# TestBench_rev3.net
KiCad netlist of a schematic drawn in EAGLE
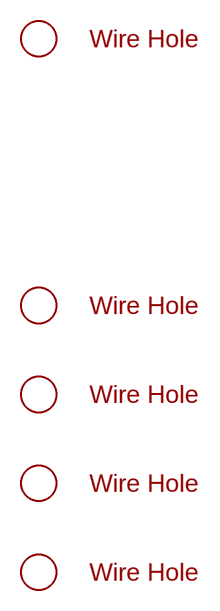
[diagram p0: schematic, sheet 1, part 1 of 2]
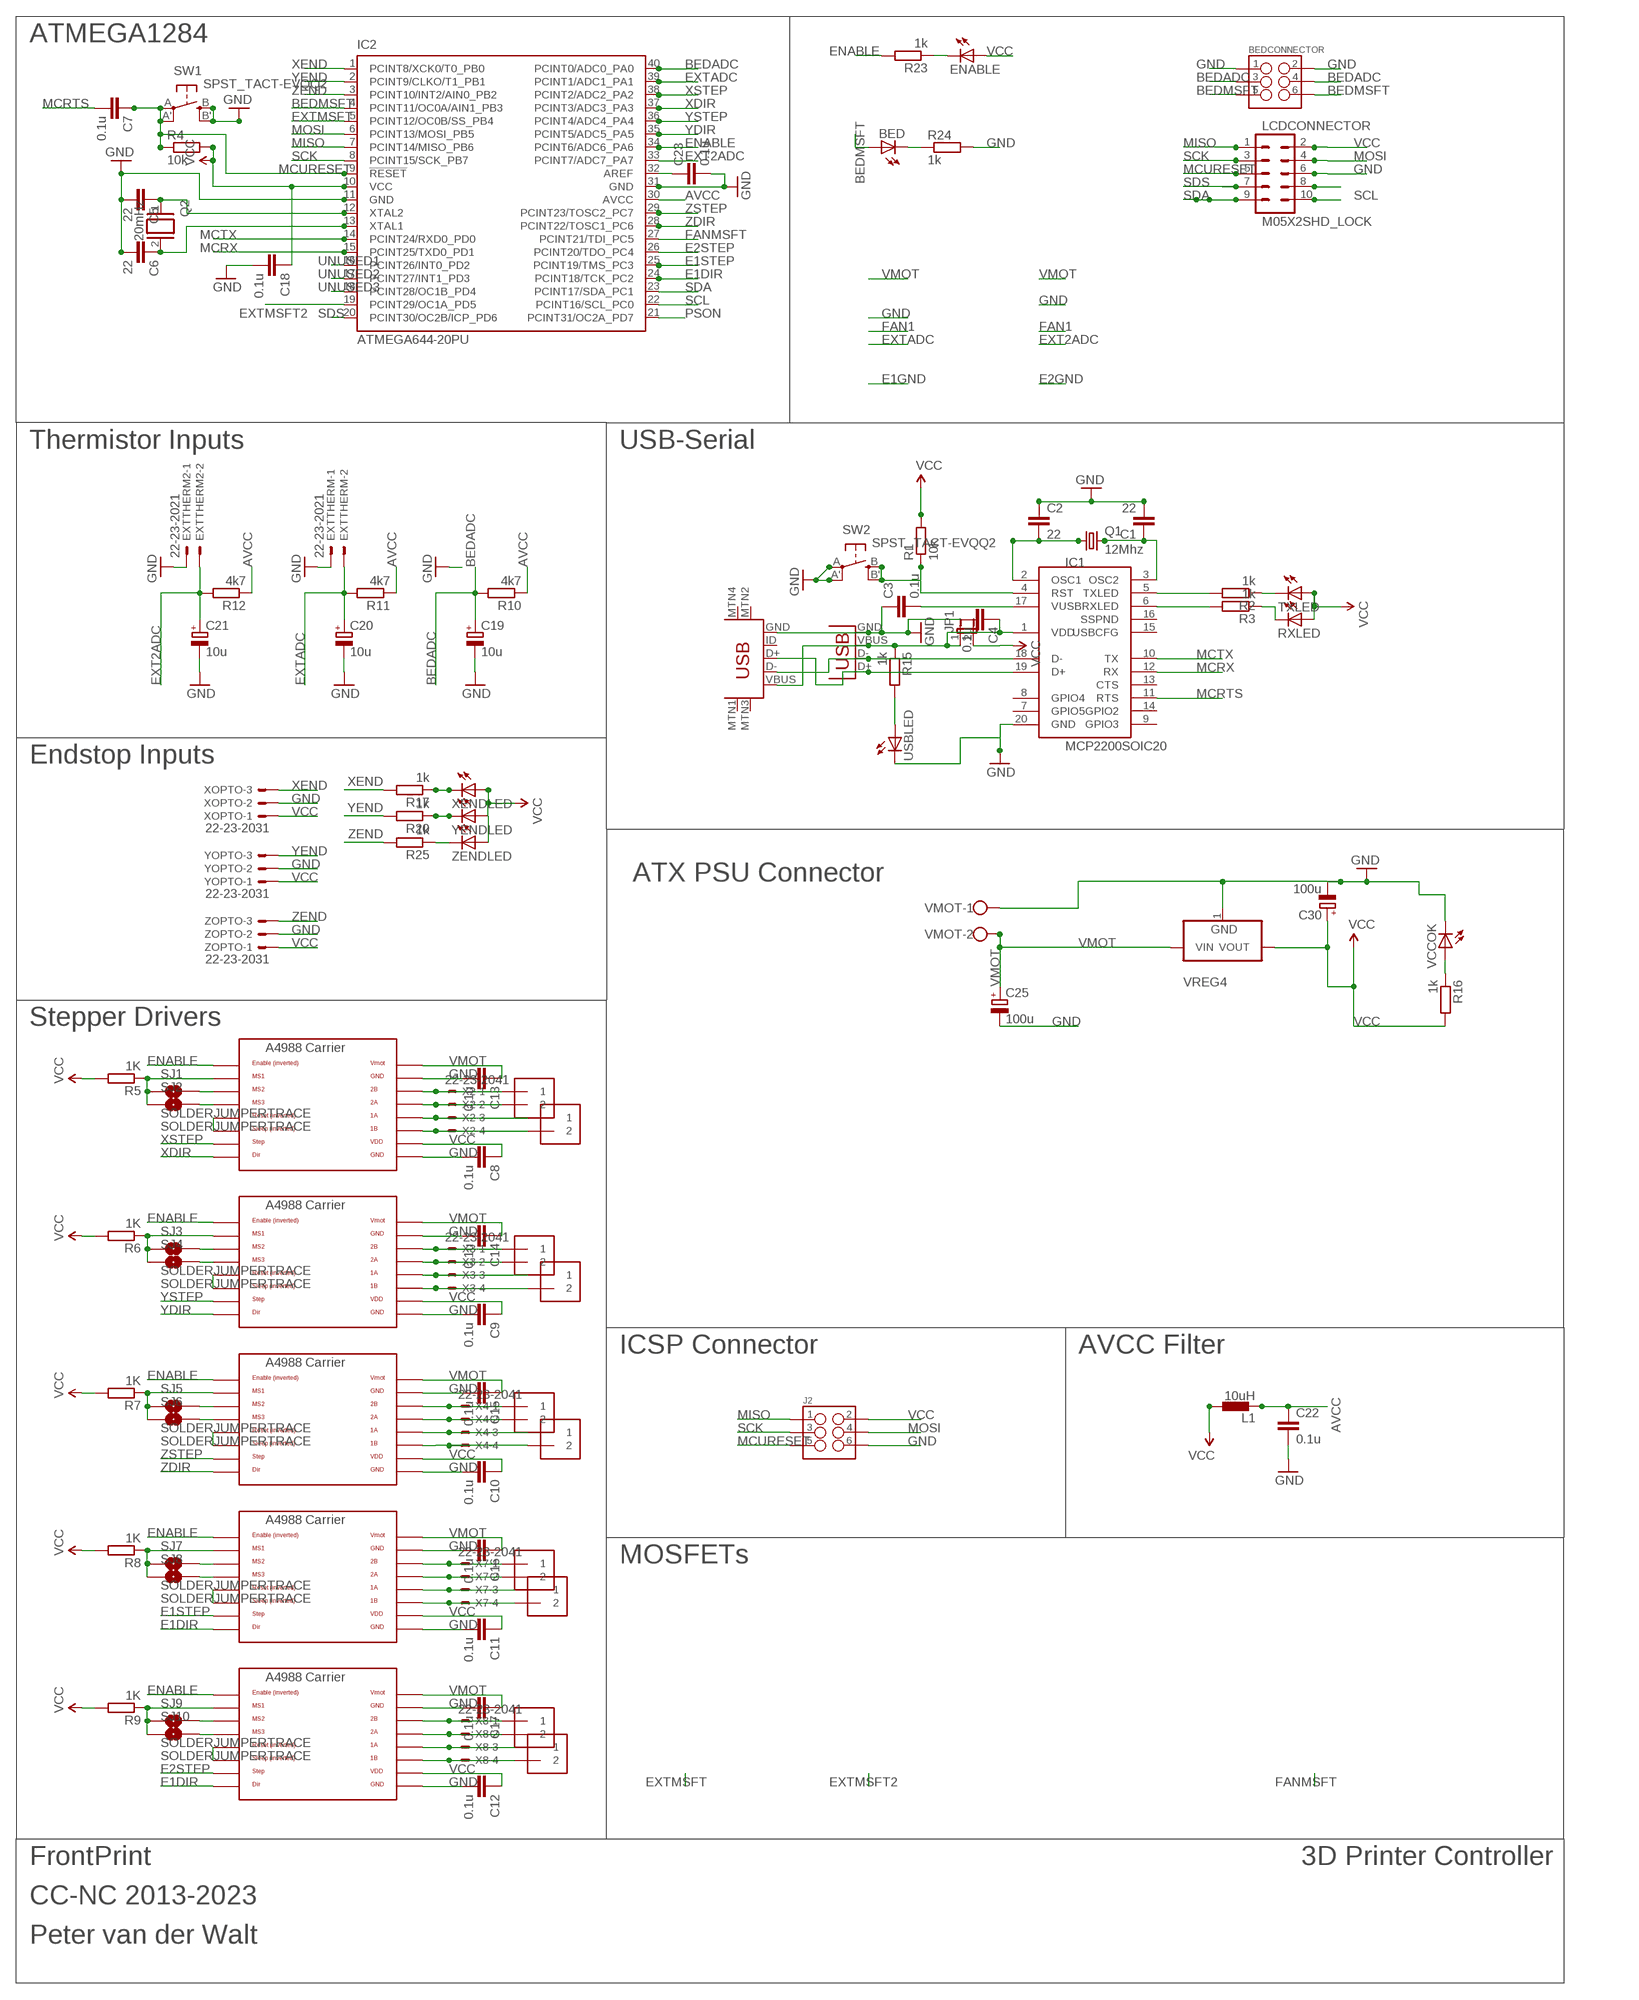
[diagram p1: schematic, sheet 1, part 2 of 2]

(export (version "E")
  (design (tool "Eeschema 10.0.6"))
  (components
    (comp (ref "BED")
      (value "LEDSMT1206")
      (footprint "eagle-import:1206")
      (libsource (lib "eagle-import") (part "LEDSMT1206"))
    )
    (comp (ref "BEDCONNECTOR")
      (value "M03X2")
      (footprint "eagle-import:2X3-SHROUDED")
      (libsource (lib "eagle-import") (part "M03X2"))
    )
    (comp (ref "C1")
      (value "22")
      (footprint "eagle-import:1206")
      (libsource (lib "eagle-import") (part "CAP1206"))
    )
    (comp (ref "C2")
      (value "22")
      (footprint "eagle-import:1206")
      (libsource (lib "eagle-import") (part "CAP1206"))
    )
    (comp (ref "C3")
      (value "0.1u")
      (footprint "eagle-import:1206")
      (libsource (lib "eagle-import") (part "CAP1206"))
    )
    (comp (ref "C4")
      (value "0.1u")
      (footprint "eagle-import:1206")
      (libsource (lib "eagle-import") (part "CAP1206"))
    )
    (comp (ref "C5")
      (value "22")
      (footprint "eagle-import:1206")
      (libsource (lib "eagle-import") (part "CAP1206"))
    )
    (comp (ref "C6")
      (value "22")
      (footprint "eagle-import:1206")
      (libsource (lib "eagle-import") (part "CAP1206"))
    )
    (comp (ref "C7")
      (value "0.1u")
      (footprint "eagle-import:1206")
      (libsource (lib "eagle-import") (part "CAP1206"))
    )
    (comp (ref "C8")
      (value "0.1u")
      (footprint "eagle-import:1206")
      (libsource (lib "eagle-import") (part "CAP1206"))
    )
    (comp (ref "C9")
      (value "0.1u")
      (footprint "eagle-import:1206")
      (libsource (lib "eagle-import") (part "CAP1206"))
    )
    (comp (ref "C10")
      (value "0.1u")
      (footprint "eagle-import:1206")
      (libsource (lib "eagle-import") (part "CAP1206"))
    )
    (comp (ref "C11")
      (value "0.1u")
      (footprint "eagle-import:1206")
      (libsource (lib "eagle-import") (part "CAP1206"))
    )
    (comp (ref "C12")
      (value "0.1u")
      (footprint "eagle-import:1206")
      (libsource (lib "eagle-import") (part "CAP1206"))
    )
    (comp (ref "C13")
      (value "0.1u")
      (footprint "eagle-import:1206")
      (libsource (lib "eagle-import") (part "CAP1206"))
    )
    (comp (ref "C14")
      (value "0.1u")
      (footprint "eagle-import:1206")
      (libsource (lib "eagle-import") (part "CAP1206"))
    )
    (comp (ref "C15")
      (value "0.1u")
      (footprint "eagle-import:1206")
      (libsource (lib "eagle-import") (part "CAP1206"))
    )
    (comp (ref "C16")
      (value "0.1u")
      (footprint "eagle-import:1206")
      (libsource (lib "eagle-import") (part "CAP1206"))
    )
    (comp (ref "C17")
      (value "0.1u")
      (footprint "eagle-import:1206")
      (libsource (lib "eagle-import") (part "CAP1206"))
    )
    (comp (ref "C18")
      (value "0.1u")
      (footprint "eagle-import:1206")
      (libsource (lib "eagle-import") (part "CAP1206"))
    )
    (comp (ref "C19")
      (value "10u")
      (footprint "eagle-import:E2,5-5")
      (libsource (lib "eagle-import") (part "CPOL-EUE2.5-5"))
    )
    (comp (ref "C20")
      (value "10u")
      (footprint "eagle-import:E2,5-5")
      (libsource (lib "eagle-import") (part "CPOL-EUE2.5-5"))
    )
    (comp (ref "C21")
      (value "10u")
      (footprint "eagle-import:E2,5-5")
      (libsource (lib "eagle-import") (part "CPOL-EUE2.5-5"))
    )
    (comp (ref "C22")
      (value "0.1u")
      (footprint "eagle-import:1206")
      (libsource (lib "eagle-import") (part "CAP1206"))
    )
    (comp (ref "C23")
      (value "0.1u")
      (footprint "eagle-import:1206")
      (libsource (lib "eagle-import") (part "CAP1206"))
    )
    (comp (ref "C25")
      (value "100u")
      (footprint "eagle-import:E5-8,5")
      (libsource (lib "eagle-import") (part "CPOL-EUE5-8.5"))
    )
    (comp (ref "C30")
      (value "100u")
      (footprint "eagle-import:E5-8,5")
      (libsource (lib "eagle-import") (part "CPOL-EUE5-8.5"))
    )
    (comp (ref "E1MOT1")
      (value "1X2-3.5MM")
      (footprint "eagle-import:3.5MMTERM")
      (libsource (lib "eagle-import") (part "1X2-3.5MM"))
    )
    (comp (ref "E1MOT2")
      (value "1X2-3.5MM")
      (footprint "eagle-import:3.5MMTERM")
      (libsource (lib "eagle-import") (part "1X2-3.5MM"))
    )
    (comp (ref "E2MOT1")
      (value "1X2-3.5MM")
      (footprint "eagle-import:3.5MMTERM")
      (libsource (lib "eagle-import") (part "1X2-3.5MM"))
    )
    (comp (ref "E2MOT2")
      (value "1X2-3.5MM")
      (footprint "eagle-import:3.5MMTERM")
      (libsource (lib "eagle-import") (part "1X2-3.5MM"))
    )
    (comp (ref "ENABLE")
      (value "LEDSMT1206")
      (footprint "eagle-import:1206")
      (libsource (lib "eagle-import") (part "LEDSMT1206"))
    )
    (comp (ref "EPOLOLU")
      (value "POLOLU_A4983CARRIER")
      (footprint "eagle-import:A4988BREAKOUT")
      (libsource (lib "eagle-import") (part "POLOLU_A4983CARRIER"))
    )
    (comp (ref "EPOLOLU2")
      (value "POLOLU_A4983CARRIER")
      (footprint "eagle-import:A4988BREAKOUT")
      (libsource (lib "eagle-import") (part "POLOLU_A4983CARRIER"))
    )
    (comp (ref "EXTTHERM")
      (value "22-23-2021")
      (footprint "eagle-import:22-23-2021")
      (fields (field (name "MF") "MOLEX"))
      (libsource (lib "eagle-import") (part "22-23-2021"))
    )
    (comp (ref "EXTTHERM2")
      (value "22-23-2021")
      (footprint "eagle-import:22-23-2021")
      (fields (field (name "MF") "MOLEX"))
      (libsource (lib "eagle-import") (part "22-23-2021"))
    )
    (comp (ref "IC1")
      (value "MCP2200SOIC20")
      (footprint "eagle-import:SOIC20")
      (libsource (lib "eagle-import") (part "MCP2200SOIC20"))
    )
    (comp (ref "IC2")
      (value "ATMEGA644-20PU")
      (footprint "eagle-import:DIL40")
      (libsource (lib "eagle-import") (part "ATMEGA644-PU20"))
    )
    (comp (ref "J2")
      (value "M03X2")
      (footprint "eagle-import:2X3-SHROUDED")
      (libsource (lib "eagle-import") (part "M03X2"))
    )
    (comp (ref "JP1")
      (value "JUMPER-2PTH_LOCK")
      (footprint "eagle-import:1X02_LOCK")
      (libsource (lib "eagle-import") (part "JUMPER-2PTH_LOCK"))
    )
    (comp (ref "L1")
      (value "10uH")
      (footprint "eagle-import:BL01RN1A")
      (libsource (lib "eagle-import") (part "BL01RN1A"))
    )
    (comp (ref "LCDCONNECTOR")
      (value "M05X2SHD_LOCK")
      (footprint "eagle-import:2X5-SHROUDED_LOCK")
      (libsource (lib "eagle-import") (part "M05X2SHD_LOCK"))
    )
    (comp (ref "Q1")
      (value "12Mhz")
      (footprint "eagle-import:HC49UP")
      (libsource (lib "eagle-import") (part "CRYSTALHC49UP"))
    )
    (comp (ref "Q2")
      (value "20mHz")
      (footprint "eagle-import:QS")
      (libsource (lib "eagle-import") (part "XTAL/S"))
    )
    (comp (ref "R1")
      (value "10k")
      (footprint "eagle-import:M1206")
      (libsource (lib "eagle-import") (part "R-EU_M1206"))
    )
    (comp (ref "R2")
      (value "1k")
      (footprint "eagle-import:M1206")
      (libsource (lib "eagle-import") (part "R-EU_M1206"))
    )
    (comp (ref "R3")
      (value "1k")
      (footprint "eagle-import:M1206")
      (libsource (lib "eagle-import") (part "R-EU_M1206"))
    )
    (comp (ref "R4")
      (value "10k")
      (footprint "eagle-import:M1206")
      (libsource (lib "eagle-import") (part "R-EU_M1206"))
    )
    (comp (ref "R5")
      (value "1K")
      (footprint "eagle-import:M1206")
      (libsource (lib "eagle-import") (part "R-EU_M1206"))
    )
    (comp (ref "R6")
      (value "1K")
      (footprint "eagle-import:M1206")
      (libsource (lib "eagle-import") (part "R-EU_M1206"))
    )
    (comp (ref "R7")
      (value "1K")
      (footprint "eagle-import:M1206")
      (libsource (lib "eagle-import") (part "R-EU_M1206"))
    )
    (comp (ref "R8")
      (value "1K")
      (footprint "eagle-import:M1206")
      (libsource (lib "eagle-import") (part "R-EU_M1206"))
    )
    (comp (ref "R9")
      (value "1K")
      (footprint "eagle-import:M1206")
      (libsource (lib "eagle-import") (part "R-EU_M1206"))
    )
    (comp (ref "R10")
      (value "4k7")
      (footprint "eagle-import:M1206")
      (libsource (lib "eagle-import") (part "R-EU_M1206"))
    )
    (comp (ref "R11")
      (value "4k7")
      (footprint "eagle-import:M1206")
      (libsource (lib "eagle-import") (part "R-EU_M1206"))
    )
    (comp (ref "R12")
      (value "4k7")
      (footprint "eagle-import:M1206")
      (libsource (lib "eagle-import") (part "R-EU_M1206"))
    )
    (comp (ref "R15")
      (value "1k")
      (footprint "eagle-import:M1206")
      (libsource (lib "eagle-import") (part "R-EU_M1206"))
    )
    (comp (ref "R16")
      (value "1k")
      (footprint "eagle-import:M1206")
      (libsource (lib "eagle-import") (part "R-EU_M1206"))
    )
    (comp (ref "R17")
      (value "1k")
      (footprint "eagle-import:M1206")
      (libsource (lib "eagle-import") (part "R-EU_M1206"))
    )
    (comp (ref "R20")
      (value "1k")
      (footprint "eagle-import:M1206")
      (libsource (lib "eagle-import") (part "R-EU_M1206"))
    )
    (comp (ref "R23")
      (value "1k")
      (footprint "eagle-import:M1206")
      (libsource (lib "eagle-import") (part "R-EU_M1206"))
    )
    (comp (ref "R24")
      (value "1k")
      (footprint "eagle-import:M1206")
      (libsource (lib "eagle-import") (part "R-EU_M1206"))
    )
    (comp (ref "R25")
      (value "1k")
      (footprint "eagle-import:M1206")
      (libsource (lib "eagle-import") (part "R-EU_M1206"))
    )
    (comp (ref "RXLED")
      (value "LEDSMT1206")
      (footprint "eagle-import:1206")
      (libsource (lib "eagle-import") (part "LEDSMT1206"))
    )
    (comp (ref "SJ1")
      (value "SOLDERJUMPERTRACE")
      (footprint "eagle-import:SJ_2S-TRACE")
      (libsource (lib "eagle-import") (part "SOLDERJUMPERTRACE"))
    )
    (comp (ref "SJ2")
      (value "SOLDERJUMPERTRACE")
      (footprint "eagle-import:SJ_2S-TRACE")
      (libsource (lib "eagle-import") (part "SOLDERJUMPERTRACE"))
    )
    (comp (ref "SJ3")
      (value "SOLDERJUMPERTRACE")
      (footprint "eagle-import:SJ_2S-TRACE")
      (libsource (lib "eagle-import") (part "SOLDERJUMPERTRACE"))
    )
    (comp (ref "SJ4")
      (value "SOLDERJUMPERTRACE")
      (footprint "eagle-import:SJ_2S-TRACE")
      (libsource (lib "eagle-import") (part "SOLDERJUMPERTRACE"))
    )
    (comp (ref "SJ5")
      (value "SOLDERJUMPERTRACE")
      (footprint "eagle-import:SJ_2S-TRACE")
      (libsource (lib "eagle-import") (part "SOLDERJUMPERTRACE"))
    )
    (comp (ref "SJ6")
      (value "SOLDERJUMPERTRACE")
      (footprint "eagle-import:SJ_2S-TRACE")
      (libsource (lib "eagle-import") (part "SOLDERJUMPERTRACE"))
    )
    (comp (ref "SJ7")
      (value "SOLDERJUMPERTRACE")
      (footprint "eagle-import:SJ_2S-TRACE")
      (libsource (lib "eagle-import") (part "SOLDERJUMPERTRACE"))
    )
    (comp (ref "SJ8")
      (value "SOLDERJUMPERTRACE")
      (footprint "eagle-import:SJ_2S-TRACE")
      (libsource (lib "eagle-import") (part "SOLDERJUMPERTRACE"))
    )
    (comp (ref "SJ9")
      (value "SOLDERJUMPERTRACE")
      (footprint "eagle-import:SJ_2S-TRACE")
      (libsource (lib "eagle-import") (part "SOLDERJUMPERTRACE"))
    )
    (comp (ref "SJ10")
      (value "SOLDERJUMPERTRACE")
      (footprint "eagle-import:SJ_2S-TRACE")
      (libsource (lib "eagle-import") (part "SOLDERJUMPERTRACE"))
    )
    (comp (ref "SW1")
      (value "SPST_TACT-EVQQ2")
      (footprint "eagle-import:EVQ-Q2")
      (libsource (lib "eagle-import") (part "SPST_TACT-EVQQ2"))
    )
    (comp (ref "SW2")
      (value "SPST_TACT-EVQQ2")
      (footprint "eagle-import:EVQ-Q2")
      (libsource (lib "eagle-import") (part "SPST_TACT-EVQQ2"))
    )
    (comp (ref "TXLED")
      (value "LEDSMT1206")
      (footprint "eagle-import:1206")
      (libsource (lib "eagle-import") (part "LEDSMT1206"))
    )
    (comp (ref "U$1")
      (value "3MMHOLE")
      (footprint "eagle-import:3MMHOLE")
      (libsource (lib "eagle-import") (part "3MMHOLE"))
    )
    (comp (ref "U$2")
      (value "USB-MINIB-5PIN")
      (footprint "eagle-import:USB-MINIB")
      (libsource (lib "eagle-import") (part "USB-MINIB-5PIN"))
    )
    (comp (ref "U$5")
      (value "3MMHOLE")
      (footprint "eagle-import:3MMHOLE")
      (libsource (lib "eagle-import") (part "3MMHOLE"))
    )
    (comp (ref "U$6")
      (value "3MMHOLE")
      (footprint "eagle-import:3MMHOLE")
      (libsource (lib "eagle-import") (part "3MMHOLE"))
    )
    (comp (ref "U$7")
      (value "3MMHOLE")
      (footprint "eagle-import:3MMHOLE")
      (libsource (lib "eagle-import") (part "3MMHOLE"))
    )
    (comp (ref "U$8")
      (value "3MMHOLE")
      (footprint "eagle-import:3MMHOLE")
      (libsource (lib "eagle-import") (part "3MMHOLE"))
    )
    (comp (ref "USBLED")
      (value "LEDSMT1206")
      (footprint "eagle-import:1206")
      (libsource (lib "eagle-import") (part "LEDSMT1206"))
    )
    (comp (ref "VCCOK")
      (value "LEDSMT1206")
      (footprint "eagle-import:1206")
      (libsource (lib "eagle-import") (part "LEDSMT1206"))
    )
    (comp (ref "VMOT")
      (value "W237-102")
      (footprint "eagle-import:W237-102")
      (fields
        (field (name "MPN") "237-102")
        (field (name "MPN_1") "237-102")
        (field (name "OC_FARNELL") "unknown")
        (field (name "OC_NEWARK") "70K9898")
      )
      (libsource (lib "eagle-import") (part "W237-102"))
    )
    (comp (ref "VREG4")
      (value "VREG_3PINS-DPAK")
      (footprint "eagle-import:DPAK")
      (libsource (lib "eagle-import") (part "VREG_3PINS-DPAK"))
    )
    (comp (ref "X1")
      (value "USBPTH")
      (footprint "eagle-import:USB-B-PTH")
      (libsource (lib "eagle-import") (part "USBPTH"))
    )
    (comp (ref "X2")
      (value "22-23-2041")
      (footprint "eagle-import:22-23-2041")
      (fields (field (name "MF") "MOLEX"))
      (libsource (lib "eagle-import") (part "22-23-2041"))
    )
    (comp (ref "X3")
      (value "22-23-2041")
      (footprint "eagle-import:22-23-2041")
      (fields (field (name "MF") "MOLEX"))
      (libsource (lib "eagle-import") (part "22-23-2041"))
    )
    (comp (ref "X4")
      (value "22-23-2041")
      (footprint "eagle-import:22-23-2041")
      (fields (field (name "MF") "MOLEX"))
      (libsource (lib "eagle-import") (part "22-23-2041"))
    )
    (comp (ref "X7")
      (value "22-23-2041")
      (footprint "eagle-import:22-23-2041")
      (fields (field (name "MF") "MOLEX"))
      (libsource (lib "eagle-import") (part "22-23-2041"))
    )
    (comp (ref "X8")
      (value "22-23-2041")
      (footprint "eagle-import:22-23-2041")
      (fields (field (name "MF") "MOLEX"))
      (libsource (lib "eagle-import") (part "22-23-2041"))
    )
    (comp (ref "XENDLED")
      (value "LEDSMT1206")
      (footprint "eagle-import:1206")
      (libsource (lib "eagle-import") (part "LEDSMT1206"))
    )
    (comp (ref "XMOT1")
      (value "1X2-3.5MM")
      (footprint "eagle-import:3.5MMTERM")
      (libsource (lib "eagle-import") (part "1X2-3.5MM"))
    )
    (comp (ref "XMOT2")
      (value "1X2-3.5MM")
      (footprint "eagle-import:3.5MMTERM")
      (libsource (lib "eagle-import") (part "1X2-3.5MM"))
    )
    (comp (ref "XOPTO")
      (value "22-23-2031")
      (footprint "eagle-import:22-23-2031")
      (fields (field (name "MF") "MOLEX"))
      (libsource (lib "eagle-import") (part "22-23-2031"))
    )
    (comp (ref "XPOLOLU")
      (value "POLOLU_A4983CARRIER")
      (footprint "eagle-import:A4988BREAKOUT")
      (libsource (lib "eagle-import") (part "POLOLU_A4983CARRIER"))
    )
    (comp (ref "YENDLED")
      (value "LEDSMT1206")
      (footprint "eagle-import:1206")
      (libsource (lib "eagle-import") (part "LEDSMT1206"))
    )
    (comp (ref "YMOT1")
      (value "1X2-3.5MM")
      (footprint "eagle-import:3.5MMTERM")
      (libsource (lib "eagle-import") (part "1X2-3.5MM"))
    )
    (comp (ref "YMOT2")
      (value "1X2-3.5MM")
      (footprint "eagle-import:3.5MMTERM")
      (libsource (lib "eagle-import") (part "1X2-3.5MM"))
    )
    (comp (ref "YOPTO")
      (value "22-23-2031")
      (footprint "eagle-import:22-23-2031")
      (fields (field (name "MF") "MOLEX"))
      (libsource (lib "eagle-import") (part "22-23-2031"))
    )
    (comp (ref "YPOLOLU")
      (value "POLOLU_A4983CARRIER")
      (footprint "eagle-import:A4988BREAKOUT")
      (libsource (lib "eagle-import") (part "POLOLU_A4983CARRIER"))
    )
    (comp (ref "ZENDLED")
      (value "LEDSMT1206")
      (footprint "eagle-import:1206")
      (libsource (lib "eagle-import") (part "LEDSMT1206"))
    )
    (comp (ref "ZMOT1")
      (value "1X2-3.5MM")
      (footprint "eagle-import:3.5MMTERM")
      (libsource (lib "eagle-import") (part "1X2-3.5MM"))
    )
    (comp (ref "ZMOT2")
      (value "1X2-3.5MM")
      (footprint "eagle-import:3.5MMTERM")
      (libsource (lib "eagle-import") (part "1X2-3.5MM"))
    )
    (comp (ref "ZOPTO")
      (value "22-23-2031")
      (footprint "eagle-import:22-23-2031")
      (fields (field (name "MF") "MOLEX"))
      (libsource (lib "eagle-import") (part "22-23-2031"))
    )
    (comp (ref "ZPOLOLU")
      (value "POLOLU_A4983CARRIER")
      (footprint "eagle-import:A4988BREAKOUT")
      (libsource (lib "eagle-import") (part "POLOLU_A4983CARRIER"))
    )
  )
  (nets
    (net (code "1") (name "/AVCC") (class "Default")
      (node (ref "C22") (pin "1") (pinfunction "1_1") (pintype "passive"))
      (node (ref "IC2") (pin "30") (pinfunction "AVCC_30") (pintype "power_in"))
      (node (ref "L1") (pin "1") (pinfunction "1_1") (pintype "passive"))
      (node (ref "R10") (pin "1") (pinfunction "1_1") (pintype "passive"))
      (node (ref "R11") (pin "1") (pinfunction "1_1") (pintype "passive"))
      (node (ref "R12") (pin "1") (pinfunction "1_1") (pintype "passive"))
    )
    (net (code "2") (name "/BEDADC") (class "Default")
      (node (ref "BEDCONNECTOR") (pin "3") (pinfunction "3_3") (pintype "bidirectional"))
      (node (ref "BEDCONNECTOR") (pin "4") (pinfunction "4_4") (pintype "bidirectional"))
      (node (ref "C19") (pin "+") (pinfunction "+_+") (pintype "passive"))
      (node (ref "IC2") (pin "40") (pinfunction "PCINT0/ADC0_PA0_40") (pintype "bidirectional"))
      (node (ref "R10") (pin "2") (pinfunction "2_2") (pintype "passive"))
    )
    (net (code "3") (name "/BEDMSFT") (class "Default")
      (node (ref "BED") (pin "A") (pinfunction "A_A") (pintype "passive"))
      (node (ref "BEDCONNECTOR") (pin "5") (pinfunction "5_5") (pintype "bidirectional"))
      (node (ref "BEDCONNECTOR") (pin "6") (pinfunction "6_6") (pintype "bidirectional"))
      (node (ref "IC2") (pin "4") (pinfunction "PCINT11/OC0A/AIN1_PB3_4") (pintype "bidirectional"))
    )
    (net (code "4") (name "/E1DIR") (class "Default")
      (node (ref "EPOLOLU") (pin "DIR") (pinfunction "DIR_DIR") (pintype "input"))
      (node (ref "EPOLOLU2") (pin "DIR") (pinfunction "DIR_DIR") (pintype "input"))
      (node (ref "IC2") (pin "24") (pinfunction "PCINT18/TCK_PC2_24") (pintype "bidirectional"))
    )
    (net (code "6") (name "/E1STEP") (class "Default")
      (node (ref "EPOLOLU") (pin "STEP") (pinfunction "STEP_STEP") (pintype "input"))
      (node (ref "IC2") (pin "25") (pinfunction "PCINT19/TMS_PC3_25") (pintype "bidirectional"))
    )
    (net (code "8") (name "/E2STEP") (class "Default")
      (node (ref "EPOLOLU2") (pin "STEP") (pinfunction "STEP_STEP") (pintype "input"))
      (node (ref "IC2") (pin "26") (pinfunction "PCINT20/TDO_PC4_26") (pintype "bidirectional"))
    )
    (net (code "9") (name "/ENABLE") (class "Default")
      (node (ref "EPOLOLU") (pin "EN") (pinfunction "EN_EN") (pintype "input"))
      (node (ref "EPOLOLU2") (pin "EN") (pinfunction "EN_EN") (pintype "input"))
      (node (ref "IC2") (pin "34") (pinfunction "PCINT6/ADC6_PA6_34") (pintype "bidirectional"))
      (node (ref "R23") (pin "2") (pinfunction "2_2") (pintype "passive"))
      (node (ref "XPOLOLU") (pin "EN") (pinfunction "EN_EN") (pintype "input"))
      (node (ref "YPOLOLU") (pin "EN") (pinfunction "EN_EN") (pintype "input"))
      (node (ref "ZPOLOLU") (pin "EN") (pinfunction "EN_EN") (pintype "input"))
    )
    (net (code "10") (name "/EXT2ADC") (class "Default")
      (node (ref "C21") (pin "+") (pinfunction "+_+") (pintype "passive"))
      (node (ref "EXTTHERM2") (pin "2") (pinfunction "S_2") (pintype "passive"))
      (node (ref "IC2") (pin "33") (pinfunction "PCINT7/ADC7_PA7_33") (pintype "bidirectional"))
      (node (ref "R12") (pin "2") (pinfunction "2_2") (pintype "passive"))
    )
    (net (code "11") (name "/EXTADC") (class "Default")
      (node (ref "C20") (pin "+") (pinfunction "+_+") (pintype "passive"))
      (node (ref "EXTTHERM") (pin "2") (pinfunction "S_2") (pintype "passive"))
      (node (ref "IC2") (pin "39") (pinfunction "PCINT1/ADC1_PA1_39") (pintype "bidirectional"))
      (node (ref "R11") (pin "2") (pinfunction "2_2") (pintype "passive"))
    )
    (net (code "12") (name "/EXTMSFT") (class "Default")
      (node (ref "IC2") (pin "5") (pinfunction "PCINT12/OC0B/SS_PB4_5") (pintype "bidirectional"))
    )
    (net (code "13") (name "/EXTMSFT2") (class "Default")
      (node (ref "IC2") (pin "19") (pinfunction "PCINT29/OC1A_PD5_19") (pintype "bidirectional"))
    )
    (net (code "15") (name "/FANMSFT") (class "Default")
      (node (ref "IC2") (pin "27") (pinfunction "PCINT21/TDI_PC5_27") (pintype "bidirectional"))
    )
    (net (code "16") (name "/MCRTS") (class "Default")
      (node (ref "C7") (pin "2") (pinfunction "2_2") (pintype "passive"))
      (node (ref "IC1") (pin "11") (pinfunction "RTS_11") (pintype "bidirectional"))
    )
    (net (code "17") (name "/MCRX") (class "Default")
      (node (ref "IC1") (pin "12") (pinfunction "RX_12") (pintype "bidirectional"))
      (node (ref "IC2") (pin "15") (pinfunction "PCINT25/TXD0_PD1_15") (pintype "bidirectional"))
    )
    (net (code "18") (name "/MCTX") (class "Default")
      (node (ref "IC1") (pin "10") (pinfunction "TX_10") (pintype "bidirectional"))
      (node (ref "IC2") (pin "14") (pinfunction "PCINT24/RXD0_PD0_14") (pintype "bidirectional"))
    )
    (net (code "19") (name "/MCURESET") (class "Default")
      (node (ref "C7") (pin "1") (pinfunction "1_1") (pintype "passive"))
      (node (ref "IC2") (pin "9") (pinfunction "~{RESET}_9") (pintype "input"))
      (node (ref "J2") (pin "5") (pinfunction "5_5") (pintype "bidirectional"))
      (node (ref "LCDCONNECTOR") (pin "5") (pinfunction "5_5") (pintype "passive"))
      (node (ref "R4") (pin "1") (pinfunction "1_1") (pintype "passive"))
      (node (ref "SW1") (pin "A") (pinfunction "P_A") (pintype "passive"))
      (node (ref "SW1") (pin "A'") (pinfunction "P1_A'") (pintype "passive"))
    )
    (net (code "20") (name "/MISO") (class "Default")
      (node (ref "IC2") (pin "7") (pinfunction "PCINT14/MISO_PB6_7") (pintype "bidirectional"))
      (node (ref "J2") (pin "1") (pinfunction "1_1") (pintype "bidirectional"))
      (node (ref "LCDCONNECTOR") (pin "1") (pinfunction "1_1") (pintype "passive"))
    )
    (net (code "21") (name "/MOSI") (class "Default")
      (node (ref "IC2") (pin "6") (pinfunction "PCINT13/MOSI_PB5_6") (pintype "bidirectional"))
      (node (ref "J2") (pin "4") (pinfunction "4_4") (pintype "bidirectional"))
      (node (ref "LCDCONNECTOR") (pin "4") (pinfunction "4_4") (pintype "passive"))
    )
    (net (code "22") (name "/PSON") (class "Default")
      (node (ref "IC2") (pin "21") (pinfunction "PCINT31/OC2A_PD7_21") (pintype "bidirectional"))
    )
    (net (code "23") (name "/SCK") (class "Default")
      (node (ref "IC2") (pin "8") (pinfunction "PCINT15/SCK_PB7_8") (pintype "bidirectional"))
      (node (ref "J2") (pin "3") (pinfunction "3_3") (pintype "bidirectional"))
      (node (ref "LCDCONNECTOR") (pin "3") (pinfunction "3_3") (pintype "passive"))
    )
    (net (code "24") (name "/SCL") (class "Default")
      (node (ref "IC2") (pin "22") (pinfunction "PCINT16/SCL_PC0_22") (pintype "bidirectional"))
      (node (ref "LCDCONNECTOR") (pin "10") (pinfunction "10_10") (pintype "passive"))
    )
    (net (code "25") (name "/SDA") (class "Default")
      (node (ref "IC2") (pin "23") (pinfunction "PCINT17/SDA_PC1_23") (pintype "bidirectional"))
      (node (ref "LCDCONNECTOR") (pin "9") (pinfunction "9_9") (pintype "passive"))
    )
    (net (code "26") (name "/SDS") (class "Default")
      (node (ref "IC2") (pin "20") (pinfunction "PCINT30/OC2B/ICP_PD6_20") (pintype "bidirectional"))
      (node (ref "LCDCONNECTOR") (pin "7") (pinfunction "7_7") (pintype "passive"))
    )
    (net (code "27") (name "/UNUSED1") (class "Default")
      (node (ref "IC2") (pin "16") (pinfunction "PCINT26/INT0_PD2_16") (pintype "bidirectional"))
    )
    (net (code "28") (name "/UNUSED2") (class "Default")
      (node (ref "IC2") (pin "17") (pinfunction "PCINT27/INT1_PD3_17") (pintype "bidirectional"))
    )
    (net (code "29") (name "/UNUSED3") (class "Default")
      (node (ref "IC2") (pin "18") (pinfunction "PCINT28/OC1B_PD4_18") (pintype "bidirectional"))
    )
    (net (code "30") (name "/VMOT") (class "Default")
      (node (ref "C13") (pin "1") (pinfunction "1_1") (pintype "passive"))
      (node (ref "C14") (pin "1") (pinfunction "1_1") (pintype "passive"))
      (node (ref "C15") (pin "1") (pinfunction "1_1") (pintype "passive"))
      (node (ref "C16") (pin "1") (pinfunction "1_1") (pintype "passive"))
      (node (ref "C17") (pin "1") (pinfunction "1_1") (pintype "passive"))
      (node (ref "C25") (pin "+") (pinfunction "+_+") (pintype "passive"))
      (node (ref "EPOLOLU") (pin "VMOT") (pinfunction "VMOT_VMOT") (pintype "power_in"))
      (node (ref "EPOLOLU2") (pin "VMOT") (pinfunction "VMOT_VMOT") (pintype "power_in"))
      (node (ref "VMOT") (pin "2") (pinfunction "KL_2") (pintype "passive"))
      (node (ref "VREG4") (pin "3") (pinfunction "VIN_3") (pintype "bidirectional"))
      (node (ref "XPOLOLU") (pin "VMOT") (pinfunction "VMOT_VMOT") (pintype "power_in"))
      (node (ref "YPOLOLU") (pin "VMOT") (pinfunction "VMOT_VMOT") (pintype "power_in"))
      (node (ref "ZPOLOLU") (pin "VMOT") (pinfunction "VMOT_VMOT") (pintype "power_in"))
    )
    (net (code "31") (name "/XDIR") (class "Default")
      (node (ref "IC2") (pin "37") (pinfunction "PCINT3/ADC3_PA3_37") (pintype "bidirectional"))
      (node (ref "XPOLOLU") (pin "DIR") (pinfunction "DIR_DIR") (pintype "input"))
    )
    (net (code "32") (name "/XEND") (class "Default")
      (node (ref "IC2") (pin "1") (pinfunction "PCINT8/XCK0/T0_PB0_1") (pintype "bidirectional"))
      (node (ref "R17") (pin "2") (pinfunction "2_2") (pintype "passive"))
      (node (ref "XOPTO") (pin "3") (pinfunction "S_3") (pintype "passive"))
    )
    (net (code "33") (name "/XSTEP") (class "Default")
      (node (ref "IC2") (pin "38") (pinfunction "PCINT2/ADC2_PA2_38") (pintype "bidirectional"))
      (node (ref "XPOLOLU") (pin "STEP") (pinfunction "STEP_STEP") (pintype "input"))
    )
    (net (code "34") (name "/YDIR") (class "Default")
      (node (ref "IC2") (pin "35") (pinfunction "PCINT5/ADC5_PA5_35") (pintype "bidirectional"))
      (node (ref "YPOLOLU") (pin "DIR") (pinfunction "DIR_DIR") (pintype "input"))
    )
    (net (code "35") (name "/YEND") (class "Default")
      (node (ref "IC2") (pin "2") (pinfunction "PCINT9/CLKO/T1_PB1_2") (pintype "bidirectional"))
      (node (ref "R20") (pin "2") (pinfunction "2_2") (pintype "passive"))
      (node (ref "YOPTO") (pin "3") (pinfunction "S_3") (pintype "passive"))
    )
    (net (code "36") (name "/YSTEP") (class "Default")
      (node (ref "IC2") (pin "36") (pinfunction "PCINT4/ADC4_PA4_36") (pintype "bidirectional"))
      (node (ref "YPOLOLU") (pin "STEP") (pinfunction "STEP_STEP") (pintype "input"))
    )
    (net (code "37") (name "/ZDIR") (class "Default")
      (node (ref "IC2") (pin "28") (pinfunction "PCINT22/TOSC1_PC6_28") (pintype "bidirectional"))
      (node (ref "ZPOLOLU") (pin "DIR") (pinfunction "DIR_DIR") (pintype "input"))
    )
    (net (code "38") (name "/ZEND") (class "Default")
      (node (ref "IC2") (pin "3") (pinfunction "PCINT10/INT2/AIN0_PB2_3") (pintype "bidirectional"))
      (node (ref "R25") (pin "2") (pinfunction "2_2") (pintype "passive"))
      (node (ref "ZOPTO") (pin "3") (pinfunction "S_3") (pintype "passive"))
    )
    (net (code "39") (name "/ZSTEP") (class "Default")
      (node (ref "IC2") (pin "29") (pinfunction "PCINT23/TOSC2_PC7_29") (pintype "bidirectional"))
      (node (ref "ZPOLOLU") (pin "STEP") (pinfunction "STEP_STEP") (pintype "input"))
    )
    (net (code "40") (name "GND") (class "Default")
      (node (ref "BEDCONNECTOR") (pin "1") (pinfunction "1_1") (pintype "bidirectional"))
      (node (ref "BEDCONNECTOR") (pin "2") (pinfunction "2_2") (pintype "bidirectional"))
      (node (ref "C1") (pin "2") (pinfunction "2_2") (pintype "passive"))
      (node (ref "C10") (pin "2") (pinfunction "2_2") (pintype "passive"))
      (node (ref "C11") (pin "2") (pinfunction "2_2") (pintype "passive"))
      (node (ref "C12") (pin "2") (pinfunction "2_2") (pintype "passive"))
      (node (ref "C13") (pin "2") (pinfunction "2_2") (pintype "passive"))
      (node (ref "C14") (pin "2") (pinfunction "2_2") (pintype "passive"))
      (node (ref "C15") (pin "2") (pinfunction "2_2") (pintype "passive"))
      (node (ref "C16") (pin "2") (pinfunction "2_2") (pintype "passive"))
      (node (ref "C17") (pin "2") (pinfunction "2_2") (pintype "passive"))
      (node (ref "C18") (pin "2") (pinfunction "2_2") (pintype "passive"))
      (node (ref "C19") (pin "-") (pinfunction "-_-") (pintype "passive"))
      (node (ref "C2") (pin "1") (pinfunction "1_1") (pintype "passive"))
      (node (ref "C20") (pin "-") (pinfunction "-_-") (pintype "passive"))
      (node (ref "C21") (pin "-") (pinfunction "-_-") (pintype "passive"))
      (node (ref "C22") (pin "2") (pinfunction "2_2") (pintype "passive"))
      (node (ref "C23") (pin "2") (pinfunction "2_2") (pintype "passive"))
      (node (ref "C25") (pin "-") (pinfunction "-_-") (pintype "passive"))
      (node (ref "C3") (pin "1") (pinfunction "1_1") (pintype "passive"))
      (node (ref "C30") (pin "-") (pinfunction "-_-") (pintype "passive"))
      (node (ref "C4") (pin "2") (pinfunction "2_2") (pintype "passive"))
      (node (ref "C5") (pin "2") (pinfunction "2_2") (pintype "passive"))
      (node (ref "C6") (pin "2") (pinfunction "2_2") (pintype "passive"))
      (node (ref "C8") (pin "2") (pinfunction "2_2") (pintype "passive"))
      (node (ref "C9") (pin "2") (pinfunction "2_2") (pintype "passive"))
      (node (ref "EPOLOLU") (pin "GND") (pinfunction "GND_GND") (pintype "power_in"))
      (node (ref "EPOLOLU") (pin "GND@0") (pinfunction "GND_GND@0") (pintype "power_in"))
      (node (ref "EPOLOLU2") (pin "GND") (pinfunction "GND_GND") (pintype "power_in"))
      (node (ref "EPOLOLU2") (pin "GND@0") (pinfunction "GND_GND@0") (pintype "power_in"))
      (node (ref "EXTTHERM") (pin "1") (pinfunction "S_1") (pintype "passive"))
      (node (ref "EXTTHERM2") (pin "1") (pinfunction "S_1") (pintype "passive"))
      (node (ref "IC1") (pin "20") (pinfunction "GND_20") (pintype "bidirectional"))
      (node (ref "IC2") (pin "11") (pinfunction "GND_11") (pintype "power_in"))
      (node (ref "IC2") (pin "31") (pinfunction "GND_31") (pintype "power_in"))
      (node (ref "J2") (pin "6") (pinfunction "6_6") (pintype "bidirectional"))
      (node (ref "LCDCONNECTOR") (pin "6") (pinfunction "6_6") (pintype "passive"))
      (node (ref "R24") (pin "2") (pinfunction "2_2") (pintype "passive"))
      (node (ref "SW1") (pin "B") (pinfunction "S_B") (pintype "passive"))
      (node (ref "SW1") (pin "B'") (pinfunction "S1_B'") (pintype "passive"))
      (node (ref "SW2") (pin "A") (pinfunction "P_A") (pintype "passive"))
      (node (ref "SW2") (pin "A'") (pinfunction "P1_A'") (pintype "passive"))
      (node (ref "U$2") (pin "GND") (pinfunction "GND_GND") (pintype "bidirectional"))
      (node (ref "USBLED") (pin "C") (pinfunction "C_C") (pintype "passive"))
      (node (ref "VCCOK") (pin "C") (pinfunction "C_C") (pintype "passive"))
      (node (ref "VMOT") (pin "1") (pinfunction "KL_1") (pintype "passive"))
      (node (ref "VREG4") (pin "1") (pinfunction "GND_1") (pintype "bidirectional"))
      (node (ref "X1") (pin "GND") (pinfunction "GND_GND") (pintype "bidirectional"))
      (node (ref "XOPTO") (pin "2") (pinfunction "S_2") (pintype "passive"))
      (node (ref "XPOLOLU") (pin "GND") (pinfunction "GND_GND") (pintype "power_in"))
      (node (ref "XPOLOLU") (pin "GND@0") (pinfunction "GND_GND@0") (pintype "power_in"))
      (node (ref "YOPTO") (pin "2") (pinfunction "S_2") (pintype "passive"))
      (node (ref "YPOLOLU") (pin "GND") (pinfunction "GND_GND") (pintype "power_in"))
      (node (ref "YPOLOLU") (pin "GND@0") (pinfunction "GND_GND@0") (pintype "power_in"))
      (node (ref "ZOPTO") (pin "2") (pinfunction "S_2") (pintype "passive"))
      (node (ref "ZPOLOLU") (pin "GND") (pinfunction "GND_GND") (pintype "power_in"))
      (node (ref "ZPOLOLU") (pin "GND@0") (pinfunction "GND_GND@0") (pintype "power_in"))
    )
    (net (code "41") (name "Net-(BED-PadC)") (class "Default")
      (node (ref "BED") (pin "C") (pinfunction "C_C") (pintype "passive"))
      (node (ref "R24") (pin "1") (pinfunction "1_1") (pintype "passive"))
    )
    (net (code "42") (name "Net-(ENABLE-PadC)") (class "Default")
      (node (ref "ENABLE") (pin "C") (pinfunction "C_C") (pintype "passive"))
      (node (ref "R23") (pin "1") (pinfunction "1_1") (pintype "passive"))
    )
    (net (code "43") (name "Net-(EPOLOLU-PadMS1)") (class "Default")
      (node (ref "EPOLOLU") (pin "MS1") (pinfunction "MS1_MS1") (pintype "input"))
      (node (ref "R8") (pin "1") (pinfunction "1_1") (pintype "passive"))
      (node (ref "SJ7") (pin "1") (pinfunction "1_1") (pintype "passive"))
      (node (ref "SJ8") (pin "1") (pinfunction "1_1") (pintype "passive"))
    )
    (net (code "44") (name "Net-(EPOLOLU-PadMS2)") (class "Default")
      (node (ref "EPOLOLU") (pin "MS2") (pinfunction "MS2_MS2") (pintype "input"))
      (node (ref "SJ7") (pin "2") (pinfunction "2_2") (pintype "passive"))
    )
    (net (code "45") (name "Net-(EPOLOLU-PadMS3)") (class "Default")
      (node (ref "EPOLOLU") (pin "MS3") (pinfunction "MS3_MS3") (pintype "input"))
      (node (ref "SJ8") (pin "2") (pinfunction "2_2") (pintype "passive"))
    )
    (net (code "46") (name "Net-(EPOLOLU-SLEEP)") (class "Default")
      (node (ref "EPOLOLU") (pin "RST") (pinfunction "RST_RST") (pintype "input"))
      (node (ref "EPOLOLU") (pin "SLP") (pinfunction "SLEEP_SLP") (pintype "input"))
    )
    (net (code "47") (name "Net-(EPOLOLU2-PadMS1)") (class "Default")
      (node (ref "EPOLOLU2") (pin "MS1") (pinfunction "MS1_MS1") (pintype "input"))
      (node (ref "R9") (pin "1") (pinfunction "1_1") (pintype "passive"))
      (node (ref "SJ10") (pin "1") (pinfunction "1_1") (pintype "passive"))
      (node (ref "SJ9") (pin "1") (pinfunction "1_1") (pintype "passive"))
    )
    (net (code "48") (name "Net-(EPOLOLU2-PadMS2)") (class "Default")
      (node (ref "EPOLOLU2") (pin "MS2") (pinfunction "MS2_MS2") (pintype "input"))
      (node (ref "SJ9") (pin "2") (pinfunction "2_2") (pintype "passive"))
    )
    (net (code "49") (name "Net-(EPOLOLU2-PadMS3)") (class "Default")
      (node (ref "EPOLOLU2") (pin "MS3") (pinfunction "MS3_MS3") (pintype "input"))
      (node (ref "SJ10") (pin "2") (pinfunction "2_2") (pintype "passive"))
    )
    (net (code "50") (name "Net-(EPOLOLU2-SLEEP)") (class "Default")
      (node (ref "EPOLOLU2") (pin "RST") (pinfunction "RST_RST") (pintype "input"))
      (node (ref "EPOLOLU2") (pin "SLP") (pinfunction "SLEEP_SLP") (pintype "input"))
    )
    (net (code "51") (name "Net-(IC1-D+)") (class "Default")
      (node (ref "IC1") (pin "19") (pinfunction "D+_19") (pintype "bidirectional"))
      (node (ref "U$2") (pin "D+") (pinfunction "D+_D+") (pintype "bidirectional"))
      (node (ref "X1") (pin "D+") (pinfunction "D+_D+") (pintype "bidirectional"))
    )
    (net (code "52") (name "Net-(IC1-D-)") (class "Default")
      (node (ref "IC1") (pin "18") (pinfunction "D-_18") (pintype "bidirectional"))
      (node (ref "U$2") (pin "D-") (pinfunction "D-_D-") (pintype "bidirectional"))
      (node (ref "X1") (pin "D-") (pinfunction "D-_D-") (pintype "bidirectional"))
    )
    (net (code "53") (name "Net-(IC1-OSC1)") (class "Default")
      (node (ref "C2") (pin "2") (pinfunction "2_2") (pintype "passive"))
      (node (ref "IC1") (pin "2") (pinfunction "OSC1_2") (pintype "bidirectional"))
      (node (ref "Q1") (pin "1") (pinfunction "1_1") (pintype "passive"))
    )
    (net (code "54") (name "Net-(IC1-OSC2)") (class "Default")
      (node (ref "C1") (pin "1") (pinfunction "1_1") (pintype "passive"))
      (node (ref "IC1") (pin "3") (pinfunction "OSC2_3") (pintype "bidirectional"))
      (node (ref "Q1") (pin "2") (pinfunction "2_2") (pintype "passive"))
    )
    (net (code "55") (name "Net-(IC1-RST)") (class "Default")
      (node (ref "IC1") (pin "4") (pinfunction "RST_4") (pintype "bidirectional"))
      (node (ref "R1") (pin "1") (pinfunction "1_1") (pintype "passive"))
      (node (ref "SW2") (pin "B") (pinfunction "S_B") (pintype "passive"))
      (node (ref "SW2") (pin "B'") (pinfunction "S1_B'") (pintype "passive"))
    )
    (net (code "56") (name "Net-(IC1-RXLED)") (class "Default")
      (node (ref "IC1") (pin "6") (pinfunction "RXLED_6") (pintype "bidirectional"))
      (node (ref "R3") (pin "2") (pinfunction "2_2") (pintype "passive"))
    )
    (net (code "57") (name "Net-(IC1-TXLED)") (class "Default")
      (node (ref "IC1") (pin "5") (pinfunction "TXLED_5") (pintype "bidirectional"))
      (node (ref "R2") (pin "2") (pinfunction "2_2") (pintype "passive"))
    )
    (net (code "58") (name "Net-(IC1-VDD)") (class "Default")
      (node (ref "C4") (pin "1") (pinfunction "1_1") (pintype "passive"))
      (node (ref "IC1") (pin "1") (pinfunction "VDD_1") (pintype "bidirectional"))
      (node (ref "JP1") (pin "1") (pinfunction "1_1") (pintype "passive"))
      (node (ref "R15") (pin "1") (pinfunction "1_1") (pintype "passive"))
      (node (ref "U$2") (pin "VBUS") (pinfunction "VBUS_VBUS") (pintype "bidirectional"))
      (node (ref "X1") (pin "VBUS") (pinfunction "VBUS_VBUS") (pintype "bidirectional"))
    )
    (net (code "59") (name "Net-(IC1-VUSB)") (class "Default")
      (node (ref "C3") (pin "2") (pinfunction "2_2") (pintype "passive"))
      (node (ref "IC1") (pin "17") (pinfunction "VUSB_17") (pintype "bidirectional"))
    )
    (net (code "60") (name "Net-(IC2-AREF)") (class "Default")
      (node (ref "C23") (pin "1") (pinfunction "1_1") (pintype "passive"))
      (node (ref "IC2") (pin "32") (pinfunction "AREF_32") (pintype "passive"))
    )
    (net (code "61") (name "Net-(IC2-XTAL1)") (class "Default")
      (node (ref "C6") (pin "1") (pinfunction "1_1") (pintype "passive"))
      (node (ref "IC2") (pin "13") (pinfunction "XTAL1_13") (pintype "input"))
      (node (ref "Q2") (pin "2") (pinfunction "2_2") (pintype "passive"))
    )
    (net (code "62") (name "Net-(IC2-XTAL2)") (class "Default")
      (node (ref "C5") (pin "1") (pinfunction "1_1") (pintype "passive"))
      (node (ref "IC2") (pin "12") (pinfunction "XTAL2_12") (pintype "output"))
      (node (ref "Q2") (pin "1") (pinfunction "1_1") (pintype "passive"))
    )
    (net (code "63") (name "Net-(R2-Pad1)") (class "Default")
      (node (ref "R2") (pin "1") (pinfunction "1_1") (pintype "passive"))
      (node (ref "TXLED") (pin "C") (pinfunction "C_C") (pintype "passive"))
    )
    (net (code "64") (name "Net-(R3-Pad1)") (class "Default")
      (node (ref "R3") (pin "1") (pinfunction "1_1") (pintype "passive"))
      (node (ref "RXLED") (pin "C") (pinfunction "C_C") (pintype "passive"))
    )
    (net (code "65") (name "Net-(R5-Pad1)") (class "Default")
      (node (ref "R5") (pin "1") (pinfunction "1_1") (pintype "passive"))
      (node (ref "SJ1") (pin "1") (pinfunction "1_1") (pintype "passive"))
      (node (ref "SJ2") (pin "1") (pinfunction "1_1") (pintype "passive"))
      (node (ref "XPOLOLU") (pin "MS1") (pinfunction "MS1_MS1") (pintype "input"))
    )
    (net (code "66") (name "Net-(R6-Pad1)") (class "Default")
      (node (ref "R6") (pin "1") (pinfunction "1_1") (pintype "passive"))
      (node (ref "SJ3") (pin "1") (pinfunction "1_1") (pintype "passive"))
      (node (ref "SJ4") (pin "1") (pinfunction "1_1") (pintype "passive"))
      (node (ref "YPOLOLU") (pin "MS1") (pinfunction "MS1_MS1") (pintype "input"))
    )
    (net (code "67") (name "Net-(R7-Pad1)") (class "Default")
      (node (ref "R7") (pin "1") (pinfunction "1_1") (pintype "passive"))
      (node (ref "SJ5") (pin "1") (pinfunction "1_1") (pintype "passive"))
      (node (ref "SJ6") (pin "1") (pinfunction "1_1") (pintype "passive"))
      (node (ref "ZPOLOLU") (pin "MS1") (pinfunction "MS1_MS1") (pintype "input"))
    )
    (net (code "68") (name "Net-(R15-Pad2)") (class "Default")
      (node (ref "R15") (pin "2") (pinfunction "2_2") (pintype "passive"))
      (node (ref "USBLED") (pin "A") (pinfunction "A_A") (pintype "passive"))
    )
    (net (code "69") (name "Net-(R16-Pad1)") (class "Default")
      (node (ref "R16") (pin "1") (pinfunction "1_1") (pintype "passive"))
      (node (ref "VCCOK") (pin "A") (pinfunction "A_A") (pintype "passive"))
    )
    (net (code "70") (name "Net-(R17-Pad1)") (class "Default")
      (node (ref "R17") (pin "1") (pinfunction "1_1") (pintype "passive"))
      (node (ref "XENDLED") (pin "C") (pinfunction "C_C") (pintype "passive"))
    )
    (net (code "71") (name "Net-(R20-Pad1)") (class "Default")
      (node (ref "R20") (pin "1") (pinfunction "1_1") (pintype "passive"))
      (node (ref "YENDLED") (pin "C") (pinfunction "C_C") (pintype "passive"))
    )
    (net (code "72") (name "Net-(R25-Pad1)") (class "Default")
      (node (ref "R25") (pin "1") (pinfunction "1_1") (pintype "passive"))
      (node (ref "ZENDLED") (pin "C") (pinfunction "C_C") (pintype "passive"))
    )
    (net (code "73") (name "Net-(SJ1-Pad2)") (class "Default")
      (node (ref "SJ1") (pin "2") (pinfunction "2_2") (pintype "passive"))
      (node (ref "XPOLOLU") (pin "MS2") (pinfunction "MS2_MS2") (pintype "input"))
    )
    (net (code "74") (name "Net-(SJ2-Pad2)") (class "Default")
      (node (ref "SJ2") (pin "2") (pinfunction "2_2") (pintype "passive"))
      (node (ref "XPOLOLU") (pin "MS3") (pinfunction "MS3_MS3") (pintype "input"))
    )
    (net (code "75") (name "Net-(SJ3-Pad2)") (class "Default")
      (node (ref "SJ3") (pin "2") (pinfunction "2_2") (pintype "passive"))
      (node (ref "YPOLOLU") (pin "MS2") (pinfunction "MS2_MS2") (pintype "input"))
    )
    (net (code "76") (name "Net-(SJ4-Pad2)") (class "Default")
      (node (ref "SJ4") (pin "2") (pinfunction "2_2") (pintype "passive"))
      (node (ref "YPOLOLU") (pin "MS3") (pinfunction "MS3_MS3") (pintype "input"))
    )
    (net (code "77") (name "Net-(SJ5-Pad2)") (class "Default")
      (node (ref "SJ5") (pin "2") (pinfunction "2_2") (pintype "passive"))
      (node (ref "ZPOLOLU") (pin "MS2") (pinfunction "MS2_MS2") (pintype "input"))
    )
    (net (code "78") (name "Net-(SJ6-Pad2)") (class "Default")
      (node (ref "SJ6") (pin "2") (pinfunction "2_2") (pintype "passive"))
      (node (ref "ZPOLOLU") (pin "MS3") (pinfunction "MS3_MS3") (pintype "input"))
    )
    (net (code "79") (name "Net-(X2A-S)") (class "Default")
      (node (ref "X2") (pin "1") (pinfunction "S_1") (pintype "passive"))
      (node (ref "XMOT1") (pin "1") (pinfunction "1_1") (pintype "passive"))
      (node (ref "XPOLOLU") (pin "2B") (pinfunction "2B_2B") (pintype "output"))
    )
    (net (code "80") (name "Net-(X2B-S)") (class "Default")
      (node (ref "X2") (pin "2") (pinfunction "S_2") (pintype "passive"))
      (node (ref "XMOT1") (pin "2") (pinfunction "2_2") (pintype "passive"))
      (node (ref "XPOLOLU") (pin "2A") (pinfunction "2A_2A") (pintype "output"))
    )
    (net (code "81") (name "Net-(X2C-S)") (class "Default")
      (node (ref "X2") (pin "3") (pinfunction "S_3") (pintype "passive"))
      (node (ref "XMOT2") (pin "1") (pinfunction "1_1") (pintype "passive"))
      (node (ref "XPOLOLU") (pin "1A") (pinfunction "1A_1A") (pintype "output"))
    )
    (net (code "82") (name "Net-(X2D-S)") (class "Default")
      (node (ref "X2") (pin "4") (pinfunction "S_4") (pintype "passive"))
      (node (ref "XMOT2") (pin "2") (pinfunction "2_2") (pintype "passive"))
      (node (ref "XPOLOLU") (pin "1B") (pinfunction "1B_1B") (pintype "output"))
    )
    (net (code "83") (name "Net-(X3A-S)") (class "Default")
      (node (ref "X3") (pin "1") (pinfunction "S_1") (pintype "passive"))
      (node (ref "YMOT1") (pin "1") (pinfunction "1_1") (pintype "passive"))
      (node (ref "YPOLOLU") (pin "2B") (pinfunction "2B_2B") (pintype "output"))
    )
    (net (code "84") (name "Net-(X3B-S)") (class "Default")
      (node (ref "X3") (pin "2") (pinfunction "S_2") (pintype "passive"))
      (node (ref "YMOT1") (pin "2") (pinfunction "2_2") (pintype "passive"))
      (node (ref "YPOLOLU") (pin "2A") (pinfunction "2A_2A") (pintype "output"))
    )
    (net (code "85") (name "Net-(X3C-S)") (class "Default")
      (node (ref "X3") (pin "3") (pinfunction "S_3") (pintype "passive"))
      (node (ref "YMOT2") (pin "1") (pinfunction "1_1") (pintype "passive"))
      (node (ref "YPOLOLU") (pin "1A") (pinfunction "1A_1A") (pintype "output"))
    )
    (net (code "86") (name "Net-(X3D-S)") (class "Default")
      (node (ref "X3") (pin "4") (pinfunction "S_4") (pintype "passive"))
      (node (ref "YMOT2") (pin "2") (pinfunction "2_2") (pintype "passive"))
      (node (ref "YPOLOLU") (pin "1B") (pinfunction "1B_1B") (pintype "output"))
    )
    (net (code "87") (name "Net-(X4A-S)") (class "Default")
      (node (ref "X4") (pin "1") (pinfunction "S_1") (pintype "passive"))
      (node (ref "ZMOT1") (pin "1") (pinfunction "1_1") (pintype "passive"))
      (node (ref "ZPOLOLU") (pin "2B") (pinfunction "2B_2B") (pintype "output"))
    )
    (net (code "88") (name "Net-(X4B-S)") (class "Default")
      (node (ref "X4") (pin "2") (pinfunction "S_2") (pintype "passive"))
      (node (ref "ZMOT1") (pin "2") (pinfunction "2_2") (pintype "passive"))
      (node (ref "ZPOLOLU") (pin "2A") (pinfunction "2A_2A") (pintype "output"))
    )
    (net (code "89") (name "Net-(X4C-S)") (class "Default")
      (node (ref "X4") (pin "3") (pinfunction "S_3") (pintype "passive"))
      (node (ref "ZMOT2") (pin "1") (pinfunction "1_1") (pintype "passive"))
      (node (ref "ZPOLOLU") (pin "1A") (pinfunction "1A_1A") (pintype "output"))
    )
    (net (code "90") (name "Net-(X4D-S)") (class "Default")
      (node (ref "X4") (pin "4") (pinfunction "S_4") (pintype "passive"))
      (node (ref "ZMOT2") (pin "2") (pinfunction "2_2") (pintype "passive"))
      (node (ref "ZPOLOLU") (pin "1B") (pinfunction "1B_1B") (pintype "output"))
    )
    (net (code "91") (name "Net-(X7A-S)") (class "Default")
      (node (ref "E1MOT1") (pin "1") (pinfunction "1_1") (pintype "passive"))
      (node (ref "EPOLOLU") (pin "2B") (pinfunction "2B_2B") (pintype "output"))
      (node (ref "X7") (pin "1") (pinfunction "S_1") (pintype "passive"))
    )
    (net (code "92") (name "Net-(X7B-S)") (class "Default")
      (node (ref "E1MOT1") (pin "2") (pinfunction "2_2") (pintype "passive"))
      (node (ref "EPOLOLU") (pin "2A") (pinfunction "2A_2A") (pintype "output"))
      (node (ref "X7") (pin "2") (pinfunction "S_2") (pintype "passive"))
    )
    (net (code "93") (name "Net-(X7C-S)") (class "Default")
      (node (ref "E1MOT2") (pin "1") (pinfunction "1_1") (pintype "passive"))
      (node (ref "EPOLOLU") (pin "1A") (pinfunction "1A_1A") (pintype "output"))
      (node (ref "X7") (pin "3") (pinfunction "S_3") (pintype "passive"))
    )
    (net (code "94") (name "Net-(X7D-S)") (class "Default")
      (node (ref "E1MOT2") (pin "2") (pinfunction "2_2") (pintype "passive"))
      (node (ref "EPOLOLU") (pin "1B") (pinfunction "1B_1B") (pintype "output"))
      (node (ref "X7") (pin "4") (pinfunction "S_4") (pintype "passive"))
    )
    (net (code "95") (name "Net-(X8A-S)") (class "Default")
      (node (ref "E2MOT1") (pin "1") (pinfunction "1_1") (pintype "passive"))
      (node (ref "EPOLOLU2") (pin "2B") (pinfunction "2B_2B") (pintype "output"))
      (node (ref "X8") (pin "1") (pinfunction "S_1") (pintype "passive"))
    )
    (net (code "96") (name "Net-(X8B-S)") (class "Default")
      (node (ref "E2MOT1") (pin "2") (pinfunction "2_2") (pintype "passive"))
      (node (ref "EPOLOLU2") (pin "2A") (pinfunction "2A_2A") (pintype "output"))
      (node (ref "X8") (pin "2") (pinfunction "S_2") (pintype "passive"))
    )
    (net (code "97") (name "Net-(X8C-S)") (class "Default")
      (node (ref "E2MOT2") (pin "1") (pinfunction "1_1") (pintype "passive"))
      (node (ref "EPOLOLU2") (pin "1A") (pinfunction "1A_1A") (pintype "output"))
      (node (ref "X8") (pin "3") (pinfunction "S_3") (pintype "passive"))
    )
    (net (code "98") (name "Net-(X8D-S)") (class "Default")
      (node (ref "E2MOT2") (pin "2") (pinfunction "2_2") (pintype "passive"))
      (node (ref "EPOLOLU2") (pin "1B") (pinfunction "1B_1B") (pintype "output"))
      (node (ref "X8") (pin "4") (pinfunction "S_4") (pintype "passive"))
    )
    (net (code "99") (name "Net-(XPOLOLU-SLEEP)") (class "Default")
      (node (ref "XPOLOLU") (pin "RST") (pinfunction "RST_RST") (pintype "input"))
      (node (ref "XPOLOLU") (pin "SLP") (pinfunction "SLEEP_SLP") (pintype "input"))
    )
    (net (code "100") (name "Net-(YPOLOLU-SLEEP)") (class "Default")
      (node (ref "YPOLOLU") (pin "RST") (pinfunction "RST_RST") (pintype "input"))
      (node (ref "YPOLOLU") (pin "SLP") (pinfunction "SLEEP_SLP") (pintype "input"))
    )
    (net (code "101") (name "Net-(ZPOLOLU-SLEEP)") (class "Default")
      (node (ref "ZPOLOLU") (pin "RST") (pinfunction "RST_RST") (pintype "input"))
      (node (ref "ZPOLOLU") (pin "SLP") (pinfunction "SLEEP_SLP") (pintype "input"))
    )
    (net (code "102") (name "VCC") (class "Default")
      (node (ref "C10") (pin "1") (pinfunction "1_1") (pintype "passive"))
      (node (ref "C11") (pin "1") (pinfunction "1_1") (pintype "passive"))
      (node (ref "C12") (pin "1") (pinfunction "1_1") (pintype "passive"))
      (node (ref "C18") (pin "1") (pinfunction "1_1") (pintype "passive"))
      (node (ref "C30") (pin "+") (pinfunction "+_+") (pintype "passive"))
      (node (ref "C8") (pin "1") (pinfunction "1_1") (pintype "passive"))
      (node (ref "C9") (pin "1") (pinfunction "1_1") (pintype "passive"))
      (node (ref "ENABLE") (pin "A") (pinfunction "A_A") (pintype "passive"))
      (node (ref "EPOLOLU") (pin "VDD") (pinfunction "VDD_VDD") (pintype "power_in"))
      (node (ref "EPOLOLU2") (pin "VDD") (pinfunction "VDD_VDD") (pintype "power_in"))
      (node (ref "IC2") (pin "10") (pinfunction "VCC_10") (pintype "power_in"))
      (node (ref "J2") (pin "2") (pinfunction "2_2") (pintype "bidirectional"))
      (node (ref "JP1") (pin "2") (pinfunction "2_2") (pintype "passive"))
      (node (ref "L1") (pin "2") (pinfunction "2_2") (pintype "passive"))
      (node (ref "LCDCONNECTOR") (pin "2") (pinfunction "2_2") (pintype "passive"))
      (node (ref "R1") (pin "2") (pinfunction "2_2") (pintype "passive"))
      (node (ref "R16") (pin "2") (pinfunction "2_2") (pintype "passive"))
      (node (ref "R4") (pin "2") (pinfunction "2_2") (pintype "passive"))
      (node (ref "R5") (pin "2") (pinfunction "2_2") (pintype "passive"))
      (node (ref "R6") (pin "2") (pinfunction "2_2") (pintype "passive"))
      (node (ref "R7") (pin "2") (pinfunction "2_2") (pintype "passive"))
      (node (ref "R8") (pin "2") (pinfunction "2_2") (pintype "passive"))
      (node (ref "R9") (pin "2") (pinfunction "2_2") (pintype "passive"))
      (node (ref "RXLED") (pin "A") (pinfunction "A_A") (pintype "passive"))
      (node (ref "TXLED") (pin "A") (pinfunction "A_A") (pintype "passive"))
      (node (ref "VREG4") (pin "2") (pinfunction "VOUT_2") (pintype "bidirectional"))
      (node (ref "XENDLED") (pin "A") (pinfunction "A_A") (pintype "passive"))
      (node (ref "XOPTO") (pin "1") (pinfunction "S_1") (pintype "passive"))
      (node (ref "XPOLOLU") (pin "VDD") (pinfunction "VDD_VDD") (pintype "power_in"))
      (node (ref "YENDLED") (pin "A") (pinfunction "A_A") (pintype "passive"))
      (node (ref "YOPTO") (pin "1") (pinfunction "S_1") (pintype "passive"))
      (node (ref "YPOLOLU") (pin "VDD") (pinfunction "VDD_VDD") (pintype "power_in"))
      (node (ref "ZENDLED") (pin "A") (pinfunction "A_A") (pintype "passive"))
      (node (ref "ZOPTO") (pin "1") (pinfunction "S_1") (pintype "passive"))
      (node (ref "ZPOLOLU") (pin "VDD") (pinfunction "VDD_VDD") (pintype "power_in"))
    )
    (net (code "103") (name "unconnected-(IC1-CTS-Pad13)") (class "Default")
      (node (ref "IC1") (pin "13") (pinfunction "CTS_13") (pintype "bidirectional"))
    )
    (net (code "104") (name "unconnected-(IC1-GPIO2-Pad14)") (class "Default")
      (node (ref "IC1") (pin "14") (pinfunction "GPIO2_14") (pintype "bidirectional"))
    )
    (net (code "105") (name "unconnected-(IC1-GPIO3-Pad9)") (class "Default")
      (node (ref "IC1") (pin "9") (pinfunction "GPIO3_9") (pintype "bidirectional"))
    )
    (net (code "106") (name "unconnected-(IC1-GPIO4-Pad8)") (class "Default")
      (node (ref "IC1") (pin "8") (pinfunction "GPIO4_8") (pintype "bidirectional"))
    )
    (net (code "107") (name "unconnected-(IC1-GPIO5-Pad7)") (class "Default")
      (node (ref "IC1") (pin "7") (pinfunction "GPIO5_7") (pintype "bidirectional"))
    )
    (net (code "108") (name "unconnected-(IC1-SSPND-Pad16)") (class "Default")
      (node (ref "IC1") (pin "16") (pinfunction "SSPND_16") (pintype "bidirectional"))
    )
    (net (code "109") (name "unconnected-(IC1-USBCFG-Pad15)") (class "Default")
      (node (ref "IC1") (pin "15") (pinfunction "USBCFG_15") (pintype "bidirectional"))
    )
    (net (code "110") (name "unconnected-(LCDCONNECTOR-Pad8)") (class "Default")
      (node (ref "LCDCONNECTOR") (pin "8") (pinfunction "8_8") (pintype "passive"))
    )
    (net (code "111") (name "unconnected-(U$2-MTN1-PadMTN3)") (class "Default")
      (node (ref "U$2") (pin "MTN3") (pinfunction "MTN1_MTN3") (pintype "bidirectional"))
    )
    (net (code "112") (name "unconnected-(U$2-MTN2-PadMTN1)") (class "Default")
      (node (ref "U$2") (pin "MTN1") (pinfunction "MTN2_MTN1") (pintype "bidirectional"))
    )
    (net (code "113") (name "unconnected-(U$2-MTN3-PadMTN2)") (class "Default")
      (node (ref "U$2") (pin "MTN2") (pinfunction "MTN3_MTN2") (pintype "bidirectional"))
    )
    (net (code "114") (name "unconnected-(U$2-PadID)") (class "Default")
      (node (ref "U$2") (pin "ID") (pinfunction "ID_ID") (pintype "bidirectional"))
    )
    (net (code "115") (name "unconnected-(U$2-PadMTN4)") (class "Default")
      (node (ref "U$2") (pin "MTN4") (pinfunction "MTN4_MTN4") (pintype "bidirectional"))
    )
  )
)
